# Sheet4.net
KiCad netlist of a schematic drawn in Altium Designer
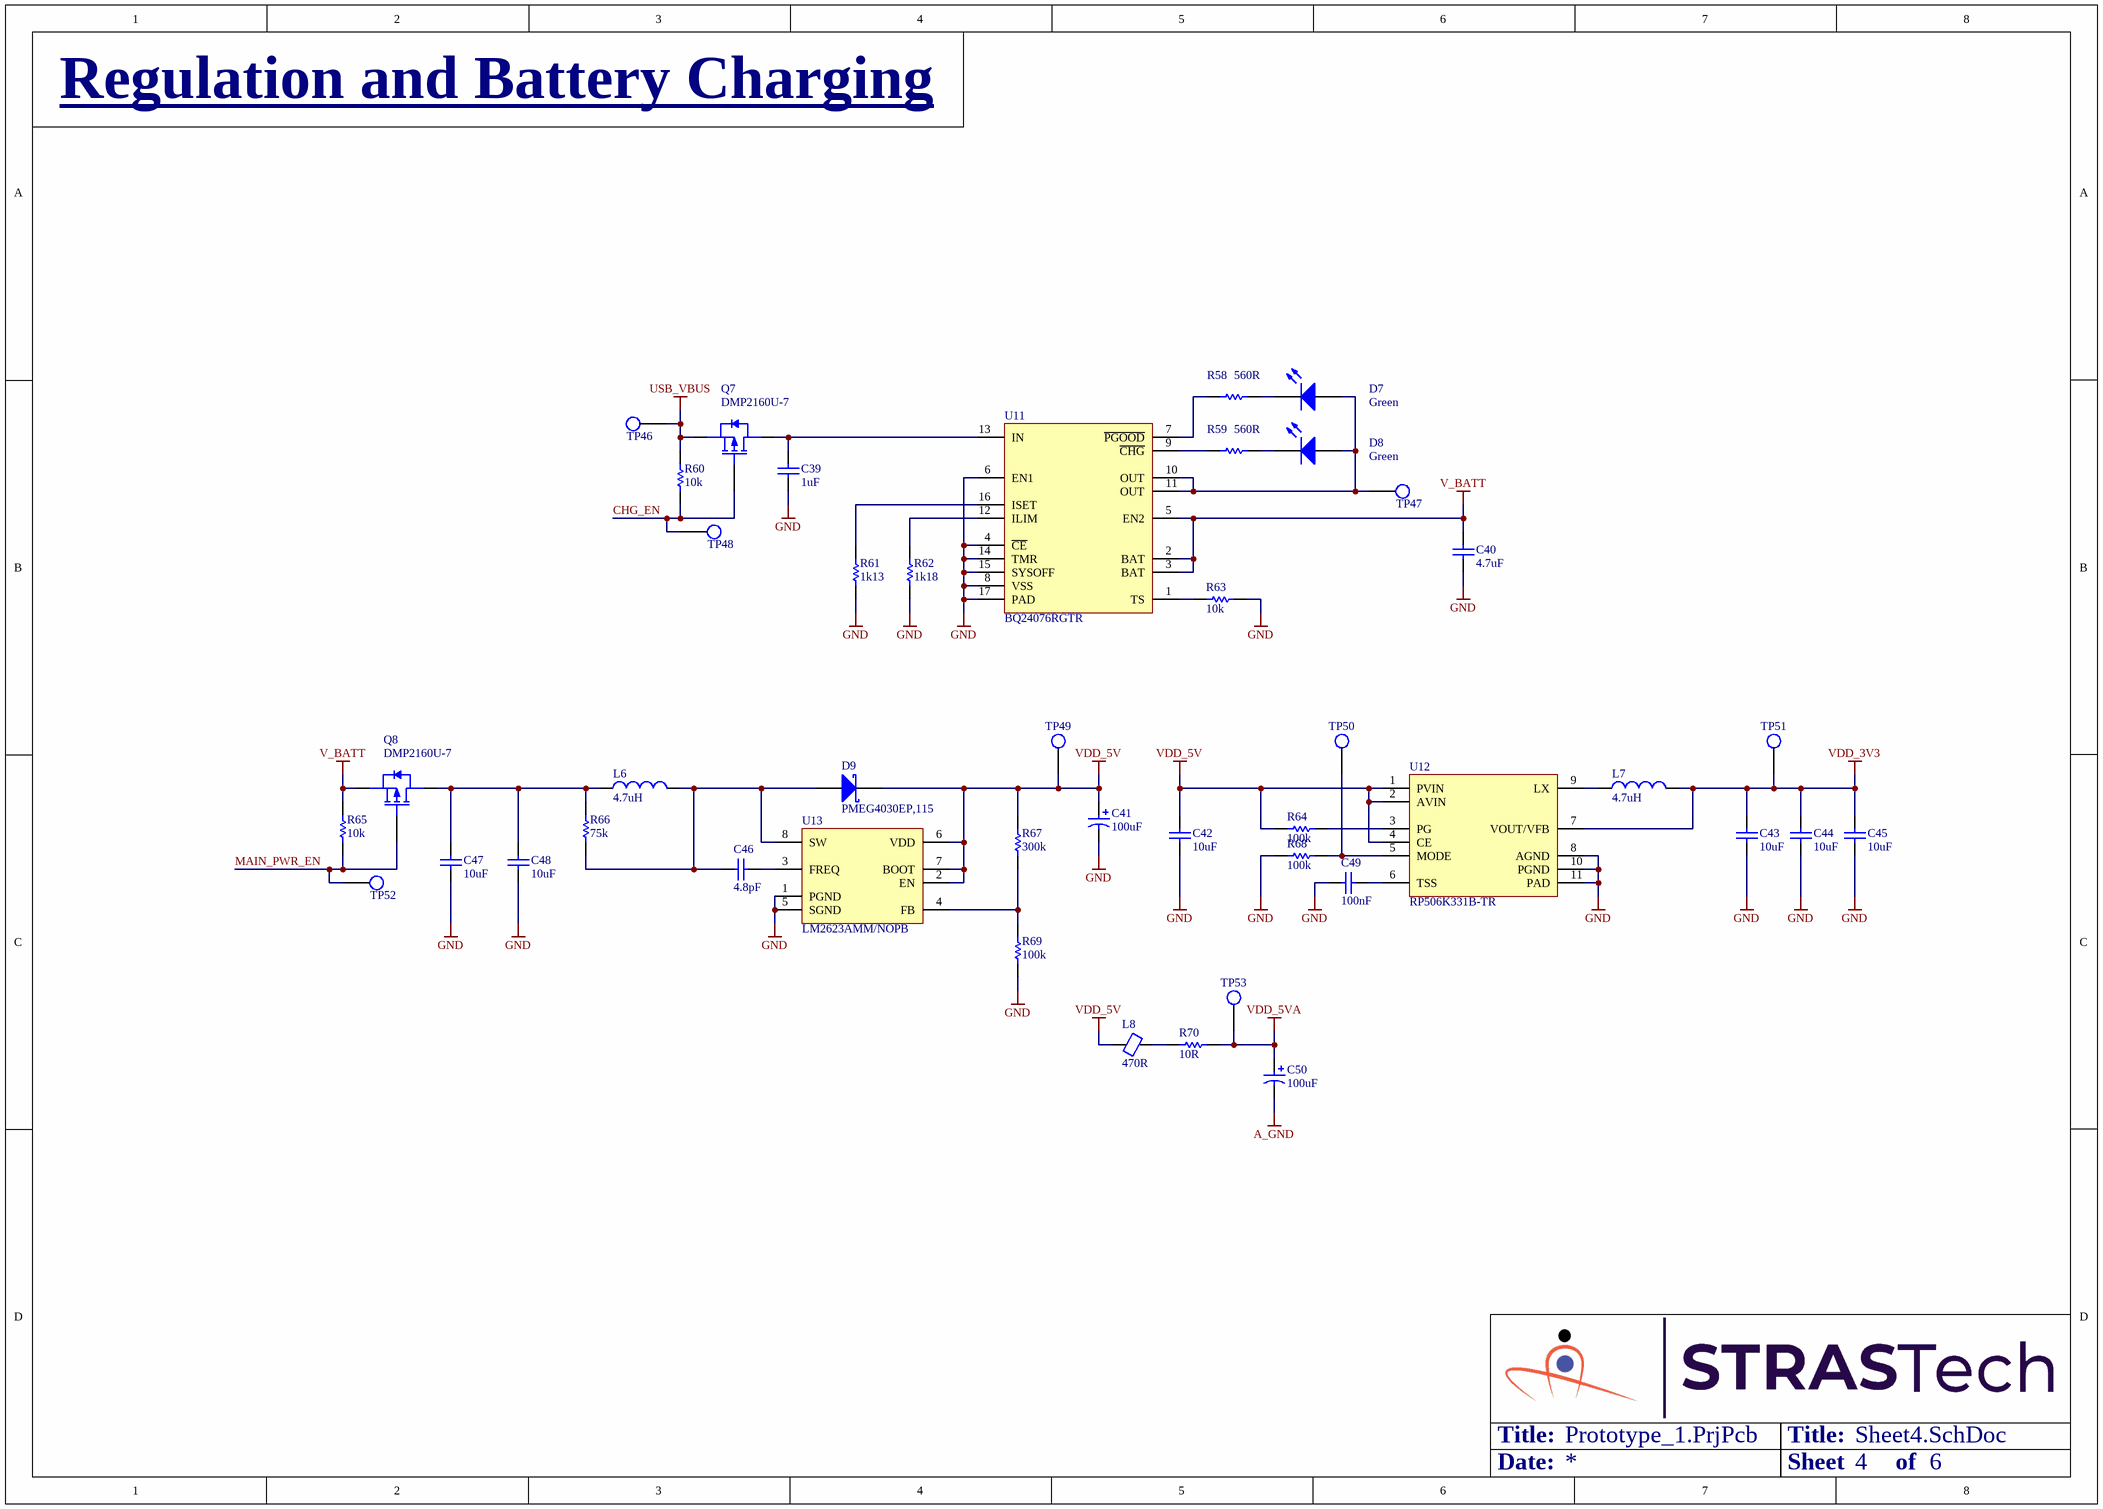
[diagram p0: Sheet4.SchDoc]

(export (version "E")
  (design (tool "Eeschema 10.0.6"))
  (components
    (comp (ref "C39")
      (value "1uF")
      (footprint "Cap,SMD,0402")
      (description "1 µF ±10% 35V Ceramic Capacitor X5R 0402 (1005 Metric)")
      (fields
        (field (name "VENDOR PART NUMBER") "445-9073-1-ND")
        (field (name "MANUFACTURER") "TDK Corporation")
        (field (name "CREATEDBY") "Judd Foster")
      )
      (libsource (lib "symbols") (part "CAP,Cer,1uF,35VDC,X5R,0402"))
    )
    (comp (ref "C40")
      (value "4.7uF")
      (footprint "Cap,SMD,0402")
      (description "4.7 µF ±20% 16V Ceramic Capacitor X5R 0402 (1005 Metric)")
      (fields
        (field (name "VENDOR PART NUMBER") "478-10788-1-ND")
        (field (name "MANUFACTURER") "AVX Corporation")
        (field (name "CREATEDBY") "Judd Foster")
      )
      (libsource (lib "symbols") (part "CAP,Cer,4.7uF,16VDC,X5R,0402"))
    )
    (comp (ref "C41")
      (value "100uF")
      (footprint "Cap,Alum,SMD,D5,H5.8")
      (description "CAP ALUM 100UF 20% 10V SMD")
      (fields
        (field (name "VENDOR PART NUMBER") "PCE3867CT-ND")
        (field (name "MANUFACTURER") "Panasonic")
        (field (name "CREATEDBY") "Judd Foster")
      )
      (libsource (lib "symbols") (part "CAP,Alum,100uF,10VDC,SMD"))
    )
    (comp (ref "C42")
      (value "10uF")
      (footprint "Cap,SMD,0402")
      (description "10 µF ±20% 10V Ceramic Capacitor X5R 0402 (1005 Metric)")
      (fields
        (field (name "VENDOR PART NUMBER") "1276-1450-1-ND")
        (field (name "MANUFACTURER") "Samsung Electro-Mechanics")
        (field (name "CREATEDBY") "Judd Foster")
      )
      (libsource (lib "symbols") (part "CAP,Cer,10uF,10VDC,X5R,0402"))
    )
    (comp (ref "C43")
      (value "10uF")
      (footprint "Cap,SMD,0402")
      (description "10 µF ±20% 10V Ceramic Capacitor X5R 0402 (1005 Metric)")
      (fields
        (field (name "VENDOR PART NUMBER") "1276-1450-1-ND")
        (field (name "MANUFACTURER") "Samsung Electro-Mechanics")
        (field (name "CREATEDBY") "Judd Foster")
      )
      (libsource (lib "symbols") (part "CAP,Cer,10uF,10VDC,X5R,0402"))
    )
    (comp (ref "C44")
      (value "10uF")
      (footprint "Cap,SMD,0402")
      (description "10 µF ±20% 10V Ceramic Capacitor X5R 0402 (1005 Metric)")
      (fields
        (field (name "VENDOR PART NUMBER") "1276-1450-1-ND")
        (field (name "MANUFACTURER") "Samsung Electro-Mechanics")
        (field (name "CREATEDBY") "Judd Foster")
      )
      (libsource (lib "symbols") (part "CAP,Cer,10uF,10VDC,X5R,0402"))
    )
    (comp (ref "C45")
      (value "10uF")
      (footprint "Cap,SMD,0402")
      (description "10 µF ±20% 10V Ceramic Capacitor X5R 0402 (1005 Metric)")
      (fields
        (field (name "VENDOR PART NUMBER") "1276-1450-1-ND")
        (field (name "MANUFACTURER") "Samsung Electro-Mechanics")
        (field (name "CREATEDBY") "Judd Foster")
      )
      (libsource (lib "symbols") (part "CAP,Cer,10uF,10VDC,X5R,0402"))
    )
    (comp (ref "C46")
      (value "4.8pF")
      (footprint "Cap,SMD,0402")
      (description "4.8 pF ±0.25pF 50V Ceramic Capacitor C0G, NP0 0402 (1005 Metric)")
      (fields
        (field (name "VENDOR PART NUMBER") "490-17481-1-ND")
        (field (name "MANUFACTURER") "Murata Electronics")
        (field (name "CREATEDBY") "Judd Foster")
      )
      (libsource (lib "symbols") (part "CAP,Cer,4.8pF,50VDC,C0G/NP0,0402"))
    )
    (comp (ref "C47")
      (value "10uF")
      (footprint "Cap,SMD,0402")
      (description "10 µF ±20% 10V Ceramic Capacitor X5R 0402 (1005 Metric)")
      (fields
        (field (name "VENDOR PART NUMBER") "1276-1450-1-ND")
        (field (name "MANUFACTURER") "Samsung Electro-Mechanics")
        (field (name "CREATEDBY") "Judd Foster")
      )
      (libsource (lib "symbols") (part "CAP,Cer,10uF,10VDC,X5R,0402"))
    )
    (comp (ref "C48")
      (value "10uF")
      (footprint "Cap,SMD,0402")
      (description "10 µF ±20% 10V Ceramic Capacitor X5R 0402 (1005 Metric)")
      (fields
        (field (name "VENDOR PART NUMBER") "1276-1450-1-ND")
        (field (name "MANUFACTURER") "Samsung Electro-Mechanics")
        (field (name "CREATEDBY") "Judd Foster")
      )
      (libsource (lib "symbols") (part "CAP,Cer,10uF,10VDC,X5R,0402"))
    )
    (comp (ref "C49")
      (value "100nF")
      (footprint "Cap,SMD,0402")
      (description "0.1µF ±10% 25V Ceramic Capacitor X7R 0402 (1005 Metric)")
      (fields
        (field (name "VENDOR PART NUMBER") "490-14603-1-ND")
        (field (name "MANUFACTURER") "Murata Electronics")
        (field (name "CREATEDBY") "Judd Foster")
      )
      (libsource (lib "symbols") (part "CAP,Cer,100nF,25VDC,X7R,0402"))
    )
    (comp (ref "C50")
      (value "100uF")
      (footprint "Cap,Alum,SMD,D5,H5.8")
      (description "CAP ALUM 100UF 20% 10V SMD")
      (fields
        (field (name "VENDOR PART NUMBER") "PCE3867CT-ND")
        (field (name "MANUFACTURER") "Panasonic")
        (field (name "CREATEDBY") "Judd Foster")
      )
      (libsource (lib "symbols") (part "CAP,Alum,100uF,10VDC,SMD"))
    )
    (comp (ref "D7")
      (value "Green")
      (footprint "LED,0603")
      (description "Green 530nm LED Indication - Discrete 3V 0603 (1608 Metric)")
      (fields
        (field (name "MANUFACTURER") "Stanley Electric Co")
        (field (name "MANUFACTURER PART NUMBER") "THG1111C-0005-TR")
        (field (name "CREATEDBY") "Judd Foster")
      )
      (libsource (lib "symbols") (part "LED,Green,SMD,0603"))
    )
    (comp (ref "D8")
      (value "Green")
      (footprint "LED,0603")
      (description "Green 530nm LED Indication - Discrete 3V 0603 (1608 Metric)")
      (fields
        (field (name "MANUFACTURER") "Stanley Electric Co")
        (field (name "MANUFACTURER PART NUMBER") "THG1111C-0005-TR")
        (field (name "CREATEDBY") "Judd Foster")
      )
      (libsource (lib "symbols") (part "LED,Green,SMD,0603"))
    )
    (comp (ref "D9")
      (value "PMEG4030EP,115")
      (footprint "SOD128")
      (description "Diode Schottky 40V 3A Surface Mount CFP5")
      (fields
        (field (name "MANUFACTURER") "Nexperia USA Inc.")
        (field (name "VENDOR PART NUMBER") "1727-5841-1-ND")
        (field (name "CREATEDBY") "Judd Foster")
      )
      (libsource (lib "symbols") (part "DIODE,Schottky,40V,3A,SMD"))
    )
    (comp (ref "L6")
      (value "4.7uH")
      (footprint "IND,WIREWOUND,4.9x4.9,SMD")
      (description "4.7µH Shielded Wirewound Inductor 2.6A 45.5mOhm Max Nonstandard")
      (fields
        (field (name "VENDOR PART NUMBER") "587-3605-1-ND")
        (field (name "MANUFACTURER") "Taiyo Yuden")
        (field (name "CREATEDBY") "Judd Foster")
      )
      (libsource (lib "symbols") (part "IND,4.7uH,2.6A,Wirewound,SMD"))
    )
    (comp (ref "L7")
      (value "4.7uH")
      (footprint "IND,WIREWOUND,4.9x4.9,SMD")
      (description "4.7µH Shielded Wirewound Inductor 2.6A 45.5mOhm Max Nonstandard")
      (fields
        (field (name "VENDOR PART NUMBER") "587-3605-1-ND")
        (field (name "MANUFACTURER") "Taiyo Yuden")
        (field (name "CREATEDBY") "Judd Foster")
      )
      (libsource (lib "symbols") (part "IND,4.7uH,2.6A,Wirewound,SMD"))
    )
    (comp (ref "L8")
      (value "470R")
      (footprint "IND,0402")
      (description "470 Ohms @ 100 MHz 1 Power Line Ferrite Bead 0402 (1005 Metric) 1A 200mOhm")
      (fields
        (field (name "VENDOR PART NUMBER") "490-10662-1-ND")
        (field (name "MANUFACTURER") "Murata Electronics")
        (field (name "CREATEDBY") "Judd Foster")
      )
      (libsource (lib "symbols") (part "Ferrite,470R@100MHz,0402"))
    )
    (comp (ref "Q7")
      (value "DMP2160U-7")
      (footprint "SOT23-3")
      (description "P-Channel 20 V 3.2A (Ta) 1.4W (Ta) Surface Mount SOT-23-3")
      (fields
        (field (name "MANUFACTURER") "Diodes Incorporated")
        (field (name "VENDOR PART NUMBER") "DMP2160UDICT-ND")
        (field (name "CREATEDBY") "Judd Foster")
      )
      (libsource (lib "symbols") (part "MOSFET,P Ch,20V,3.2A"))
    )
    (comp (ref "Q8")
      (value "DMP2160U-7")
      (footprint "SOT23-3")
      (description "P-Channel 20 V 3.2A (Ta) 1.4W (Ta) Surface Mount SOT-23-3")
      (fields
        (field (name "MANUFACTURER") "Diodes Incorporated")
        (field (name "VENDOR PART NUMBER") "DMP2160UDICT-ND")
        (field (name "CREATEDBY") "Judd Foster")
      )
      (libsource (lib "symbols") (part "MOSFET,P Ch,20V,3.2A"))
    )
    (comp (ref "R58")
      (value "560R")
      (footprint "RES,0402")
      (fields
        (field (name "MANUFACTURER") "TE Connectivity Passive Product")
        (field (name "MANUFACTURER PART NUMBER") "CRGCQ0402F560R")
        (field (name "VENDOR PART NUMBER") "A129624CT-ND")
        (field (name "CREATEDBY") "Judd Foster")
      )
      (libsource (lib "symbols") (part "RES,560R,1%,0.063W,0402"))
    )
    (comp (ref "R59")
      (value "560R")
      (footprint "RES,0402")
      (fields
        (field (name "MANUFACTURER") "TE Connectivity Passive Product")
        (field (name "MANUFACTURER PART NUMBER") "CRGCQ0402F560R")
        (field (name "VENDOR PART NUMBER") "A129624CT-ND")
        (field (name "CREATEDBY") "Judd Foster")
      )
      (libsource (lib "symbols") (part "RES,560R,1%,0.063W,0402"))
    )
    (comp (ref "R60")
      (value "10k")
      (footprint "RES,0402")
      (description "10 kOhms ±5% 0.063W, 1/16W Chip Resistor 0402 (1005 Metric) Automotive AEC-Q200 Thick Film")
      (fields
        (field (name "VENDOR PART NUMBER") "RMCF0402JT10K0CT-ND")
        (field (name "MANUFACTURER") "Stackpole Electronics Inc")
        (field (name "CREATEDBY") "Judd Foster")
      )
      (libsource (lib "symbols") (part "RES,10k,5%,0.063W,0402"))
    )
    (comp (ref "R61")
      (value "1k13")
      (footprint "RES,0402")
      (description "1.13 kOhms ±1% 0.063W, 1/16W Chip Resistor 0402 (1005 Metric) Automotive AEC-Q200 Thick Film")
      (fields
        (field (name "MANUFACTURER") "Stackpole Electronics Inc")
        (field (name "MANUFACTURER PART NUMBER") "RMCF0402FT1K13")
        (field (name "CREATEDBY") "Judd Foster")
      )
      (libsource (lib "symbols") (part "RES,1k13,1%,0.063W,0402"))
    )
    (comp (ref "R62")
      (value "1k18")
      (footprint "RES,0402")
      (description "1.18 kOhms ±1% 0.063W, 1/16W Chip Resistor 0402 (1005 Metric) Automotive AEC-Q200 Thick Film")
      (fields
        (field (name "MANUFACTURER") "Stackpole Electronics Inc")
        (field (name "MANUFACTURER PART NUMBER") "RMCF0402FT1K18")
        (field (name "CREATEDBY") "Judd Foster")
      )
      (libsource (lib "symbols") (part "RES,1k18,1%,0.063W,0402"))
    )
    (comp (ref "R63")
      (value "10k")
      (footprint "RES,0402")
      (description "10 kOhms ±5% 0.063W, 1/16W Chip Resistor 0402 (1005 Metric) Automotive AEC-Q200 Thick Film")
      (fields
        (field (name "VENDOR PART NUMBER") "RMCF0402JT10K0CT-ND")
        (field (name "MANUFACTURER") "Stackpole Electronics Inc")
        (field (name "CREATEDBY") "Judd Foster")
      )
      (libsource (lib "symbols") (part "RES,10k,5%,0.063W,0402"))
    )
    (comp (ref "R64")
      (value "100k")
      (footprint "RES,0402")
      (description "100 kOhms ±5% 0.1W, 1/10W Chip Resistor 0402 (1005 Metric) Automotive AEC-Q200 Thick Film")
      (fields
        (field (name "MANUFACTURER") "Panasonic Electronic Components")
        (field (name "MANUFACTURER PART NUMBER") "ERJ-2GEJ104X")
        (field (name "CREATEDBY") "Judd Foster")
      )
      (libsource (lib "symbols") (part "RES,100k,5%,0.1W,0402"))
    )
    (comp (ref "R65")
      (value "10k")
      (footprint "RES,0402")
      (description "10 kOhms ±5% 0.063W, 1/16W Chip Resistor 0402 (1005 Metric) Automotive AEC-Q200 Thick Film")
      (fields
        (field (name "VENDOR PART NUMBER") "RMCF0402JT10K0CT-ND")
        (field (name "MANUFACTURER") "Stackpole Electronics Inc")
        (field (name "CREATEDBY") "Judd Foster")
      )
      (libsource (lib "symbols") (part "RES,10k,5%,0.063W,0402"))
    )
    (comp (ref "R66")
      (value "75k")
      (footprint "RES,0402")
      (description "75 kOhms ±0.1% 0.063W, 1/16W Chip Resistor 0402 (1005 Metric) - Thin Film")
      (fields
        (field (name "VENDOR PART NUMBER") "YAG4414CT-ND")
        (field (name "MANUFACTURER") "YAGEO")
        (field (name "CREATEDBY") "Judd Foster")
      )
      (libsource (lib "symbols") (part "RES,75k,0.1%,0.063W,0402"))
    )
    (comp (ref "R67")
      (value "300k")
      (footprint "RES,0402")
      (description "300 kOhms ±1% 0.063W, 1/16W Chip Resistor 0402 (1005 Metric) Automotive AEC-Q200 Thick Film")
      (fields
        (field (name "MANUFACTURER") "Stackpole Electronics Inc")
        (field (name "MANUFACTURER PART NUMBER") "RMCF0402FT300K")
        (field (name "CREATEDBY") "Judd Foster")
      )
      (libsource (lib "symbols") (part "RES,300k,1%,0.063W,0402"))
    )
    (comp (ref "R68")
      (value "100k")
      (footprint "RES,0402")
      (description "100 kOhms ±5% 0.1W, 1/10W Chip Resistor 0402 (1005 Metric) Automotive AEC-Q200 Thick Film")
      (fields
        (field (name "MANUFACTURER") "Panasonic Electronic Components")
        (field (name "MANUFACTURER PART NUMBER") "ERJ-2GEJ104X")
        (field (name "CREATEDBY") "Judd Foster")
      )
      (libsource (lib "symbols") (part "RES,100k,5%,0.1W,0402"))
    )
    (comp (ref "R69")
      (value "100k")
      (footprint "RES,0402")
      (description "100 kOhms ±5% 0.1W, 1/10W Chip Resistor 0402 (1005 Metric) Automotive AEC-Q200 Thick Film")
      (fields
        (field (name "MANUFACTURER") "Panasonic Electronic Components")
        (field (name "MANUFACTURER PART NUMBER") "ERJ-2GEJ104X")
        (field (name "CREATEDBY") "Judd Foster")
      )
      (libsource (lib "symbols") (part "RES,100k,5%,0.1W,0402"))
    )
    (comp (ref "R70")
      (value "10R")
      (footprint "RES,0402")
      (description "10 Ohms ±1% 0.063W, 1/16W Chip Resistor 0402 (1005 Metric) Automotive AEC-Q200 Thick Film")
      (fields
        (field (name "MANUFACTURER") "Panasonic Electronic Components")
        (field (name "MANUFACTURER PART NUMBER") "ERJ-2RKF10R0X")
        (field (name "CREATEDBY") "Judd Foster")
      )
      (libsource (lib "symbols") (part "RES,10R,1%,0.063W,0402"))
    )
    (comp (ref "TP46")
      (value "TESTPOINT")
      (footprint "testpoint,smd,round,1mm")
      (description "PCB Testpoint")
      (fields (field (name "CREATEDBY") "Judd Foster"))
      (libsource (lib "symbols") (part "TESTPOINT"))
    )
    (comp (ref "TP47")
      (value "TESTPOINT")
      (footprint "testpoint,smd,round,1mm")
      (description "PCB Testpoint")
      (fields (field (name "CREATEDBY") "Judd Foster"))
      (libsource (lib "symbols") (part "TESTPOINT"))
    )
    (comp (ref "TP48")
      (value "TESTPOINT")
      (footprint "testpoint,smd,round,1mm")
      (description "PCB Testpoint")
      (fields (field (name "CREATEDBY") "Judd Foster"))
      (libsource (lib "symbols") (part "TESTPOINT"))
    )
    (comp (ref "TP49")
      (value "TESTPOINT")
      (footprint "testpoint,smd,round,1mm")
      (description "PCB Testpoint")
      (fields (field (name "CREATEDBY") "Judd Foster"))
      (libsource (lib "symbols") (part "TESTPOINT"))
    )
    (comp (ref "TP50")
      (value "TESTPOINT")
      (footprint "testpoint,smd,round,1mm")
      (description "PCB Testpoint")
      (fields (field (name "CREATEDBY") "Judd Foster"))
      (libsource (lib "symbols") (part "TESTPOINT"))
    )
    (comp (ref "TP51")
      (value "TESTPOINT")
      (footprint "testpoint,smd,round,1mm")
      (description "PCB Testpoint")
      (fields (field (name "CREATEDBY") "Judd Foster"))
      (libsource (lib "symbols") (part "TESTPOINT"))
    )
    (comp (ref "TP52")
      (value "TESTPOINT")
      (footprint "testpoint,smd,round,1mm")
      (description "PCB Testpoint")
      (fields (field (name "CREATEDBY") "Judd Foster"))
      (libsource (lib "symbols") (part "TESTPOINT"))
    )
    (comp (ref "TP53")
      (value "TESTPOINT")
      (footprint "testpoint,smd,round,1mm")
      (description "PCB Testpoint")
      (fields (field (name "CREATEDBY") "Judd Foster"))
      (libsource (lib "symbols") (part "TESTPOINT"))
    )
    (comp (ref "U11")
      (value "BQ24076RGTR")
      (footprint "IC,QFN-16,3x3")
      (description "Charger IC Lithium Ion 16-VQFN (3x3)")
      (fields
        (field (name "VENDOR PART NUMBER") "296-52627-1-ND")
        (field (name "MANUFACTURER") "Texas Instruments")
        (field (name "CREATEDBY") "Judd Foster")
      )
      (libsource (lib "symbols") (part "BQ24076RGTR"))
    )
    (comp (ref "U12")
      (value "RP506K331B-TR")
      (footprint "IC,DFN-10_3x3,P0.5mm")
      (description "Buck Switching Regulator IC Positive Fixed 3.3V 1 Output 2A 10-UFDFN Exposed Pad")
      (fields
        (field (name "MANUFACTURER") "Nisshinbo Micro Devices Inc.")
        (field (name "VENDOR PART NUMBER") "2129-RP506K331B-CT-ND")
        (field (name "CREATEDBY") "Judd Foster")
      )
      (libsource (lib "symbols") (part "RP506K331B-TR"))
    )
    (comp (ref "U13")
      (value "LM2623AMM/NOPB")
      (footprint "IC,TSSOP-8,W3.0")
      (fields
        (field (name "VENDOR PART NUMBER") "LM2623AMM/NOPBCT-ND")
        (field (name "MANUFACTURER") "Texas Instruments")
        (field (name "CREATEDBY") "Judd Foster")
      )
      (libsource (lib "symbols") (part "LM2623AMM/NOPB"))
    )
  )
  (nets
    (net (code "1") (name "/CHG_EN") (class "Default")
      (node (ref "Q7") (pin "1") (pinfunction "G_1") (pintype "passive"))
      (node (ref "R60") (pin "1") (pinfunction "1_1") (pintype "passive"))
      (node (ref "TP48") (pin "1") (pinfunction "TP_1") (pintype "passive"))
    )
    (net (code "2") (name "/MAIN_PWR_EN") (class "Default")
      (node (ref "Q8") (pin "1") (pinfunction "G_1") (pintype "passive"))
      (node (ref "R65") (pin "1") (pinfunction "1_1") (pintype "passive"))
      (node (ref "TP52") (pin "1") (pinfunction "TP_1") (pintype "passive"))
    )
    (net (code "3") (name "A_GND") (class "Default")
      (node (ref "C50") (pin "2") (pinfunction "2_2") (pintype "passive"))
    )
    (net (code "4") (name "GND") (class "Default")
      (node (ref "C39") (pin "1") (pinfunction "1_1") (pintype "passive"))
      (node (ref "C40") (pin "1") (pinfunction "1_1") (pintype "passive"))
      (node (ref "C41") (pin "2") (pinfunction "2_2") (pintype "passive"))
      (node (ref "C42") (pin "1") (pinfunction "1_1") (pintype "passive"))
      (node (ref "C43") (pin "1") (pinfunction "1_1") (pintype "passive"))
      (node (ref "C44") (pin "1") (pinfunction "1_1") (pintype "passive"))
      (node (ref "C45") (pin "1") (pinfunction "1_1") (pintype "passive"))
      (node (ref "C47") (pin "1") (pinfunction "1_1") (pintype "passive"))
      (node (ref "C48") (pin "1") (pinfunction "1_1") (pintype "passive"))
      (node (ref "C49") (pin "1") (pinfunction "1_1") (pintype "passive"))
      (node (ref "R61") (pin "1") (pinfunction "1_1") (pintype "passive"))
      (node (ref "R62") (pin "1") (pinfunction "1_1") (pintype "passive"))
      (node (ref "R63") (pin "1") (pinfunction "1_1") (pintype "passive"))
      (node (ref "R68") (pin "2") (pinfunction "2_2") (pintype "passive"))
      (node (ref "R69") (pin "1") (pinfunction "1_1") (pintype "passive"))
      (node (ref "U11") (pin "14") (pinfunction "TMR_14") (pintype "passive"))
      (node (ref "U11") (pin "15") (pinfunction "SYSOFF_15") (pintype "passive"))
      (node (ref "U11") (pin "17") (pinfunction "PAD_17") (pintype "passive"))
      (node (ref "U11") (pin "4") (pinfunction "~{CE}_4") (pintype "passive"))
      (node (ref "U11") (pin "6") (pinfunction "EN1_6") (pintype "passive"))
      (node (ref "U11") (pin "8") (pinfunction "VSS_8") (pintype "passive"))
      (node (ref "U12") (pin "10") (pinfunction "PGND_10") (pintype "passive"))
      (node (ref "U12") (pin "11") (pinfunction "PAD_11") (pintype "passive"))
      (node (ref "U12") (pin "8") (pinfunction "AGND_8") (pintype "passive"))
      (node (ref "U13") (pin "1") (pinfunction "PGND_1") (pintype "passive"))
      (node (ref "U13") (pin "5") (pinfunction "SGND_5") (pintype "passive"))
    )
    (net (code "5") (name "Net-(D7-A)") (class "Default")
      (node (ref "D7") (pin "1") (pinfunction "A_1") (pintype "passive"))
      (node (ref "D8") (pin "1") (pinfunction "A_1") (pintype "passive"))
      (node (ref "TP47") (pin "1") (pinfunction "TP_1") (pintype "passive"))
      (node (ref "U11") (pin "10") (pinfunction "OUT_10") (pintype "passive"))
      (node (ref "U11") (pin "11") (pinfunction "OUT_11") (pintype "passive"))
    )
    (net (code "6") (name "Net-(D7-K)") (class "Default")
      (node (ref "D7") (pin "2") (pinfunction "K_2") (pintype "passive"))
      (node (ref "R58") (pin "2") (pinfunction "2_2") (pintype "passive"))
    )
    (net (code "7") (name "Net-(D8-K)") (class "Default")
      (node (ref "D8") (pin "2") (pinfunction "K_2") (pintype "passive"))
      (node (ref "R59") (pin "2") (pinfunction "2_2") (pintype "passive"))
    )
    (net (code "8") (name "Net-(D9-A)") (class "Default")
      (node (ref "C46") (pin "1") (pinfunction "1_1") (pintype "passive"))
      (node (ref "D9") (pin "2") (pinfunction "A_2") (pintype "passive"))
      (node (ref "L6") (pin "2") (pinfunction "2_2") (pintype "passive"))
      (node (ref "R66") (pin "1") (pinfunction "1_1") (pintype "passive"))
      (node (ref "U13") (pin "8") (pinfunction "SW_8") (pintype "passive"))
    )
    (net (code "9") (name "Net-(L8-Pad2)") (class "Default")
      (node (ref "L8") (pin "2") (pinfunction "2_2") (pintype "passive"))
      (node (ref "R70") (pin "1") (pinfunction "1_1") (pintype "passive"))
    )
    (net (code "10") (name "Net-(Q7-D)") (class "Default")
      (node (ref "C39") (pin "2") (pinfunction "2_2") (pintype "passive"))
      (node (ref "Q7") (pin "3") (pinfunction "D_3") (pintype "passive"))
      (node (ref "U11") (pin "13") (pinfunction "IN_13") (pintype "passive"))
    )
    (net (code "11") (name "Net-(Q8-D)") (class "Default")
      (node (ref "C47") (pin "2") (pinfunction "2_2") (pintype "passive"))
      (node (ref "C48") (pin "2") (pinfunction "2_2") (pintype "passive"))
      (node (ref "L6") (pin "1") (pinfunction "1_1") (pintype "passive"))
      (node (ref "Q8") (pin "3") (pinfunction "D_3") (pintype "passive"))
      (node (ref "R66") (pin "2") (pinfunction "2_2") (pintype "passive"))
    )
    (net (code "12") (name "Net-(TP50-TP)") (class "Default")
      (node (ref "R68") (pin "1") (pinfunction "1_1") (pintype "passive"))
      (node (ref "TP50") (pin "1") (pinfunction "TP_1") (pintype "passive"))
      (node (ref "U12") (pin "5") (pinfunction "MODE_5") (pintype "passive"))
    )
    (net (code "13") (name "Net-(U11-ILIM)") (class "Default")
      (node (ref "R62") (pin "2") (pinfunction "2_2") (pintype "passive"))
      (node (ref "U11") (pin "12") (pinfunction "ILIM_12") (pintype "passive"))
    )
    (net (code "14") (name "Net-(U11-ISET)") (class "Default")
      (node (ref "R61") (pin "2") (pinfunction "2_2") (pintype "passive"))
      (node (ref "U11") (pin "16") (pinfunction "ISET_16") (pintype "passive"))
    )
    (net (code "15") (name "Net-(U11-TS)") (class "Default")
      (node (ref "R63") (pin "2") (pinfunction "2_2") (pintype "passive"))
      (node (ref "U11") (pin "1") (pinfunction "TS_1") (pintype "passive"))
    )
    (net (code "16") (name "Net-(U11-~{CHG})") (class "Default")
      (node (ref "R59") (pin "1") (pinfunction "1_1") (pintype "passive"))
      (node (ref "U11") (pin "9") (pinfunction "~{CHG}_9") (pintype "passive"))
    )
    (net (code "17") (name "Net-(U11-~{PGOOD})") (class "Default")
      (node (ref "R58") (pin "1") (pinfunction "1_1") (pintype "passive"))
      (node (ref "U11") (pin "7") (pinfunction "~{PGOOD}_7") (pintype "passive"))
    )
    (net (code "18") (name "Net-(U12-LX)") (class "Default")
      (node (ref "L7") (pin "1") (pinfunction "1_1") (pintype "passive"))
      (node (ref "U12") (pin "9") (pinfunction "LX_9") (pintype "passive"))
    )
    (net (code "19") (name "Net-(U12-PG)") (class "Default")
      (node (ref "R64") (pin "1") (pinfunction "1_1") (pintype "passive"))
      (node (ref "U12") (pin "3") (pinfunction "PG_3") (pintype "passive"))
    )
    (net (code "20") (name "Net-(U12-TSS)") (class "Default")
      (node (ref "C49") (pin "2") (pinfunction "2_2") (pintype "passive"))
      (node (ref "U12") (pin "6") (pinfunction "TSS_6") (pintype "passive"))
    )
    (net (code "21") (name "Net-(U13-FB)") (class "Default")
      (node (ref "R67") (pin "1") (pinfunction "1_1") (pintype "passive"))
      (node (ref "R69") (pin "2") (pinfunction "2_2") (pintype "passive"))
      (node (ref "U13") (pin "4") (pinfunction "FB_4") (pintype "passive"))
    )
    (net (code "22") (name "Net-(U13-FREQ)") (class "Default")
      (node (ref "C46") (pin "2") (pinfunction "2_2") (pintype "passive"))
      (node (ref "U13") (pin "3") (pinfunction "FREQ_3") (pintype "passive"))
    )
    (net (code "23") (name "USB_VBUS") (class "Default")
      (node (ref "Q7") (pin "2") (pinfunction "S_2") (pintype "passive"))
      (node (ref "R60") (pin "2") (pinfunction "2_2") (pintype "passive"))
      (node (ref "TP46") (pin "1") (pinfunction "TP_1") (pintype "passive"))
    )
    (net (code "24") (name "VDD_3V3") (class "Default")
      (node (ref "C43") (pin "2") (pinfunction "2_2") (pintype "passive"))
      (node (ref "C44") (pin "2") (pinfunction "2_2") (pintype "passive"))
      (node (ref "C45") (pin "2") (pinfunction "2_2") (pintype "passive"))
      (node (ref "L7") (pin "2") (pinfunction "2_2") (pintype "passive"))
      (node (ref "TP51") (pin "1") (pinfunction "TP_1") (pintype "passive"))
      (node (ref "U12") (pin "7") (pinfunction "VOUT/VFB_7") (pintype "passive"))
    )
    (net (code "25") (name "VDD_5V") (class "Default")
      (node (ref "C41") (pin "1") (pinfunction "1_1") (pintype "passive"))
      (node (ref "C42") (pin "2") (pinfunction "2_2") (pintype "passive"))
      (node (ref "D9") (pin "1") (pinfunction "K_1") (pintype "passive"))
      (node (ref "L8") (pin "1") (pinfunction "1_1") (pintype "passive"))
      (node (ref "R64") (pin "2") (pinfunction "2_2") (pintype "passive"))
      (node (ref "R67") (pin "2") (pinfunction "2_2") (pintype "passive"))
      (node (ref "TP49") (pin "1") (pinfunction "TP_1") (pintype "passive"))
      (node (ref "U12") (pin "1") (pinfunction "PVIN_1") (pintype "passive"))
      (node (ref "U12") (pin "2") (pinfunction "AVIN_2") (pintype "passive"))
      (node (ref "U12") (pin "4") (pinfunction "CE_4") (pintype "passive"))
      (node (ref "U13") (pin "2") (pinfunction "EN_2") (pintype "passive"))
      (node (ref "U13") (pin "6") (pinfunction "VDD_6") (pintype "passive"))
      (node (ref "U13") (pin "7") (pinfunction "BOOT_7") (pintype "passive"))
    )
    (net (code "26") (name "VDD_5VA") (class "Default")
      (node (ref "C50") (pin "1") (pinfunction "1_1") (pintype "passive"))
      (node (ref "R70") (pin "2") (pinfunction "2_2") (pintype "passive"))
      (node (ref "TP53") (pin "1") (pinfunction "TP_1") (pintype "passive"))
    )
    (net (code "27") (name "V_BATT") (class "Default")
      (node (ref "C40") (pin "2") (pinfunction "2_2") (pintype "passive"))
      (node (ref "Q8") (pin "2") (pinfunction "S_2") (pintype "passive"))
      (node (ref "R65") (pin "2") (pinfunction "2_2") (pintype "passive"))
      (node (ref "U11") (pin "2") (pinfunction "BAT_2") (pintype "passive"))
      (node (ref "U11") (pin "3") (pinfunction "BAT_3") (pintype "passive"))
      (node (ref "U11") (pin "5") (pinfunction "EN2_5") (pintype "passive"))
    )
  )
)
